# BridgeSensors.net
KiCad netlist of a schematic drawn in Altium Designer
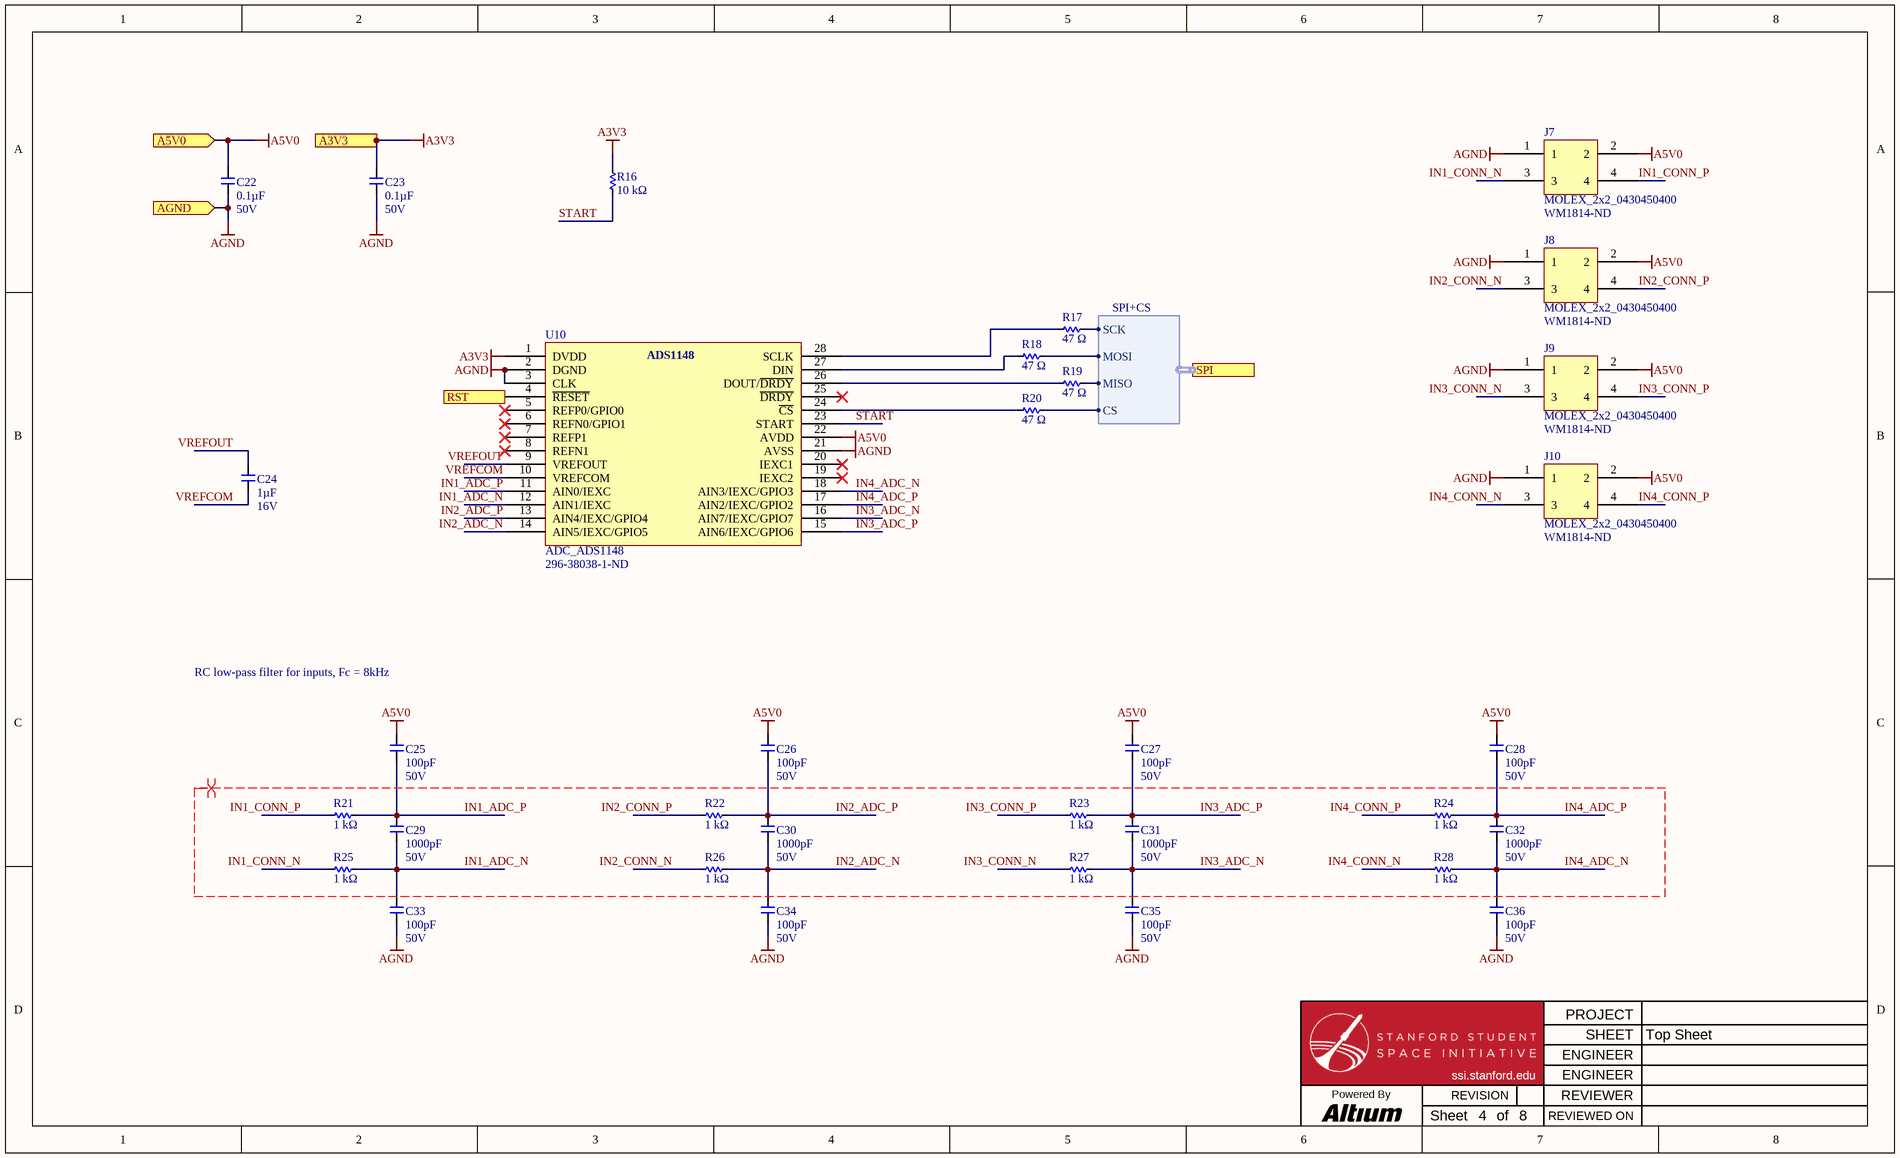
[diagram p0: BridgeSensors.SchDoc]

(export (version "E")
  (design (tool "Eeschema 10.0.6"))
  (components
    (comp (ref "C22")
      (value "__template_cap")
      (footprint "C0603")
      (description "CAP CER 0603 0.1µF X7R 50V 10%")
      (fields
        (field (name "CAPACITANCE (SHORTHAND)") "0.1µF")
        (field (name "RATED VOLTAGE") "50V")
        (field (name "MANUFACTURER") "Murata Electronics North America")
      )
      (libsource (lib "passives") (part "__template_cap"))
    )
    (comp (ref "C23")
      (value "__template_cap")
      (footprint "C0603")
      (description "CAP CER 0603 0.1µF X7R 50V 10%")
      (fields
        (field (name "CAPACITANCE (SHORTHAND)") "0.1µF")
        (field (name "RATED VOLTAGE") "50V")
        (field (name "MANUFACTURER") "Murata Electronics North America")
      )
      (libsource (lib "passives") (part "__template_cap"))
    )
    (comp (ref "C24")
      (value "__template_cap")
      (footprint "C0603")
      (description "CAP CER 0603 1µF X7R 16V 10%")
      (fields
        (field (name "CAPACITANCE (SHORTHAND)") "1µF")
        (field (name "RATED VOLTAGE") "16V")
        (field (name "MANUFACTURER") "Murata Electronics North America")
      )
      (libsource (lib "passives") (part "__template_cap"))
    )
    (comp (ref "C25")
      (value "__template_cap")
      (footprint "C0603")
      (description "CAP CER 100PF 50V C0G/NP0 0603")
      (fields
        (field (name "CAPACITANCE (SHORTHAND)") "100pF")
        (field (name "RATED VOLTAGE") "50V")
        (field (name "MANUFACTURER") "Murata Electronics North America")
      )
      (libsource (lib "passives") (part "__template_cap"))
    )
    (comp (ref "C26")
      (value "__template_cap")
      (footprint "C0603")
      (description "CAP CER 100PF 50V C0G/NP0 0603")
      (fields
        (field (name "CAPACITANCE (SHORTHAND)") "100pF")
        (field (name "RATED VOLTAGE") "50V")
        (field (name "MANUFACTURER") "Murata Electronics North America")
      )
      (libsource (lib "passives") (part "__template_cap"))
    )
    (comp (ref "C27")
      (value "__template_cap")
      (footprint "C0603")
      (description "CAP CER 100PF 50V C0G/NP0 0603")
      (fields
        (field (name "CAPACITANCE (SHORTHAND)") "100pF")
        (field (name "RATED VOLTAGE") "50V")
        (field (name "MANUFACTURER") "Murata Electronics North America")
      )
      (libsource (lib "passives") (part "__template_cap"))
    )
    (comp (ref "C28")
      (value "__template_cap")
      (footprint "C0603")
      (description "CAP CER 100PF 50V C0G/NP0 0603")
      (fields
        (field (name "CAPACITANCE (SHORTHAND)") "100pF")
        (field (name "RATED VOLTAGE") "50V")
        (field (name "MANUFACTURER") "Murata Electronics North America")
      )
      (libsource (lib "passives") (part "__template_cap"))
    )
    (comp (ref "C29")
      (value "__template_cap")
      (footprint "C0603")
      (description "CAP CER 0603 1000pF X7R 50V 10%")
      (fields
        (field (name "CAPACITANCE (SHORTHAND)") "1000pF")
        (field (name "RATED VOLTAGE") "50V")
        (field (name "MANUFACTURER") "Murata Electronics North America")
      )
      (libsource (lib "passives") (part "__template_cap"))
    )
    (comp (ref "C30")
      (value "__template_cap")
      (footprint "C0603")
      (description "CAP CER 0603 1000pF X7R 50V 10%")
      (fields
        (field (name "CAPACITANCE (SHORTHAND)") "1000pF")
        (field (name "RATED VOLTAGE") "50V")
        (field (name "MANUFACTURER") "Murata Electronics North America")
      )
      (libsource (lib "passives") (part "__template_cap"))
    )
    (comp (ref "C31")
      (value "__template_cap")
      (footprint "C0603")
      (description "CAP CER 0603 1000pF X7R 50V 10%")
      (fields
        (field (name "CAPACITANCE (SHORTHAND)") "1000pF")
        (field (name "RATED VOLTAGE") "50V")
        (field (name "MANUFACTURER") "Murata Electronics North America")
      )
      (libsource (lib "passives") (part "__template_cap"))
    )
    (comp (ref "C32")
      (value "__template_cap")
      (footprint "C0603")
      (description "CAP CER 0603 1000pF X7R 50V 10%")
      (fields
        (field (name "CAPACITANCE (SHORTHAND)") "1000pF")
        (field (name "RATED VOLTAGE") "50V")
        (field (name "MANUFACTURER") "Murata Electronics North America")
      )
      (libsource (lib "passives") (part "__template_cap"))
    )
    (comp (ref "C33")
      (value "__template_cap")
      (footprint "C0603")
      (description "CAP CER 100PF 50V C0G/NP0 0603")
      (fields
        (field (name "CAPACITANCE (SHORTHAND)") "100pF")
        (field (name "RATED VOLTAGE") "50V")
        (field (name "MANUFACTURER") "Murata Electronics North America")
      )
      (libsource (lib "passives") (part "__template_cap"))
    )
    (comp (ref "C34")
      (value "__template_cap")
      (footprint "C0603")
      (description "CAP CER 100PF 50V C0G/NP0 0603")
      (fields
        (field (name "CAPACITANCE (SHORTHAND)") "100pF")
        (field (name "RATED VOLTAGE") "50V")
        (field (name "MANUFACTURER") "Murata Electronics North America")
      )
      (libsource (lib "passives") (part "__template_cap"))
    )
    (comp (ref "C35")
      (value "__template_cap")
      (footprint "C0603")
      (description "CAP CER 100PF 50V C0G/NP0 0603")
      (fields
        (field (name "CAPACITANCE (SHORTHAND)") "100pF")
        (field (name "RATED VOLTAGE") "50V")
        (field (name "MANUFACTURER") "Murata Electronics North America")
      )
      (libsource (lib "passives") (part "__template_cap"))
    )
    (comp (ref "C36")
      (value "__template_cap")
      (footprint "C0603")
      (description "CAP CER 100PF 50V C0G/NP0 0603")
      (fields
        (field (name "CAPACITANCE (SHORTHAND)") "100pF")
        (field (name "RATED VOLTAGE") "50V")
        (field (name "MANUFACTURER") "Murata Electronics North America")
      )
      (libsource (lib "passives") (part "__template_cap"))
    )
    (comp (ref "J7")
      (value "MOLEX_2x2_0430450400")
      (footprint "MOLEX_2x2_0430450400")
      (description "MICROFIT CONN HEADER R/A 4POS 3MM")
      (fields (field (name "SUPPLIER PART NUMBER 1") "WM1814-ND"))
      (libsource (lib "SSI") (part "MOLEX_2x2_0430450400"))
    )
    (comp (ref "J8")
      (value "MOLEX_2x2_0430450400")
      (footprint "MOLEX_2x2_0430450400")
      (description "MICROFIT CONN HEADER R/A 4POS 3MM")
      (fields (field (name "SUPPLIER PART NUMBER 1") "WM1814-ND"))
      (libsource (lib "SSI") (part "MOLEX_2x2_0430450400"))
    )
    (comp (ref "J9")
      (value "MOLEX_2x2_0430450400")
      (footprint "MOLEX_2x2_0430450400")
      (description "MICROFIT CONN HEADER R/A 4POS 3MM")
      (fields (field (name "SUPPLIER PART NUMBER 1") "WM1814-ND"))
      (libsource (lib "SSI") (part "MOLEX_2x2_0430450400"))
    )
    (comp (ref "J10")
      (value "MOLEX_2x2_0430450400")
      (footprint "MOLEX_2x2_0430450400")
      (description "MICROFIT CONN HEADER R/A 4POS 3MM")
      (fields (field (name "SUPPLIER PART NUMBER 1") "WM1814-ND"))
      (libsource (lib "SSI") (part "MOLEX_2x2_0430450400"))
    )
    (comp (ref "R16")
      (value "__template_resistor")
      (footprint "R0603")
      (description "RES SMD 10K OHM 1% 1/10W 0603")
      (fields
        (field (name "RESISTANCE") "10 kΩ")
        (field (name "MANUFACTURER PART NUMBER") "RC0603FR-0710KL")
        (field (name "MANUFACTURER") "Yageo")
      )
      (libsource (lib "passives") (part "__template_resistor"))
    )
    (comp (ref "R17")
      (value "__template_resistor")
      (footprint "R0603")
      (description "RES SMD 47 OHM 1% 1/10W 0603")
      (fields
        (field (name "RESISTANCE") "47 Ω")
        (field (name "MANUFACTURER PART NUMBER") "RC0603FR-0747RL")
        (field (name "MANUFACTURER") "Yageo")
      )
      (libsource (lib "passives") (part "__template_resistor"))
    )
    (comp (ref "R18")
      (value "__template_resistor")
      (footprint "R0603")
      (description "RES SMD 47 OHM 1% 1/10W 0603")
      (fields
        (field (name "RESISTANCE") "47 Ω")
        (field (name "MANUFACTURER PART NUMBER") "RC0603FR-0747RL")
        (field (name "MANUFACTURER") "Yageo")
      )
      (libsource (lib "passives") (part "__template_resistor"))
    )
    (comp (ref "R19")
      (value "__template_resistor")
      (footprint "R0603")
      (description "RES SMD 47 OHM 1% 1/10W 0603")
      (fields
        (field (name "RESISTANCE") "47 Ω")
        (field (name "MANUFACTURER PART NUMBER") "RC0603FR-0747RL")
        (field (name "MANUFACTURER") "Yageo")
      )
      (libsource (lib "passives") (part "__template_resistor"))
    )
    (comp (ref "R20")
      (value "__template_resistor")
      (footprint "R0603")
      (description "RES SMD 47 OHM 1% 1/10W 0603")
      (fields
        (field (name "RESISTANCE") "47 Ω")
        (field (name "MANUFACTURER PART NUMBER") "RC0603FR-0747RL")
        (field (name "MANUFACTURER") "Yageo")
      )
      (libsource (lib "passives") (part "__template_resistor"))
    )
    (comp (ref "R21")
      (value "__template_resistor")
      (footprint "R0603")
      (description "RES SMD 1K OHM 1% 1/10W 0603")
      (fields
        (field (name "RESISTANCE") "1 kΩ")
        (field (name "MANUFACTURER PART NUMBER") "RC0603FR-071KL")
        (field (name "MANUFACTURER") "Yageo")
      )
      (libsource (lib "passives") (part "__template_resistor"))
    )
    (comp (ref "R22")
      (value "__template_resistor")
      (footprint "R0603")
      (description "RES SMD 1K OHM 1% 1/10W 0603")
      (fields
        (field (name "RESISTANCE") "1 kΩ")
        (field (name "MANUFACTURER PART NUMBER") "RC0603FR-071KL")
        (field (name "MANUFACTURER") "Yageo")
      )
      (libsource (lib "passives") (part "__template_resistor"))
    )
    (comp (ref "R23")
      (value "__template_resistor")
      (footprint "R0603")
      (description "RES SMD 1K OHM 1% 1/10W 0603")
      (fields
        (field (name "RESISTANCE") "1 kΩ")
        (field (name "MANUFACTURER PART NUMBER") "RC0603FR-071KL")
        (field (name "MANUFACTURER") "Yageo")
      )
      (libsource (lib "passives") (part "__template_resistor"))
    )
    (comp (ref "R24")
      (value "__template_resistor")
      (footprint "R0603")
      (description "RES SMD 1K OHM 1% 1/10W 0603")
      (fields
        (field (name "RESISTANCE") "1 kΩ")
        (field (name "MANUFACTURER PART NUMBER") "RC0603FR-071KL")
        (field (name "MANUFACTURER") "Yageo")
      )
      (libsource (lib "passives") (part "__template_resistor"))
    )
    (comp (ref "R25")
      (value "__template_resistor")
      (footprint "R0603")
      (description "RES SMD 1K OHM 1% 1/10W 0603")
      (fields
        (field (name "RESISTANCE") "1 kΩ")
        (field (name "MANUFACTURER PART NUMBER") "RC0603FR-071KL")
        (field (name "MANUFACTURER") "Yageo")
      )
      (libsource (lib "passives") (part "__template_resistor"))
    )
    (comp (ref "R26")
      (value "__template_resistor")
      (footprint "R0603")
      (description "RES SMD 1K OHM 1% 1/10W 0603")
      (fields
        (field (name "RESISTANCE") "1 kΩ")
        (field (name "MANUFACTURER PART NUMBER") "RC0603FR-071KL")
        (field (name "MANUFACTURER") "Yageo")
      )
      (libsource (lib "passives") (part "__template_resistor"))
    )
    (comp (ref "R27")
      (value "__template_resistor")
      (footprint "R0603")
      (description "RES SMD 1K OHM 1% 1/10W 0603")
      (fields
        (field (name "RESISTANCE") "1 kΩ")
        (field (name "MANUFACTURER PART NUMBER") "RC0603FR-071KL")
        (field (name "MANUFACTURER") "Yageo")
      )
      (libsource (lib "passives") (part "__template_resistor"))
    )
    (comp (ref "R28")
      (value "__template_resistor")
      (footprint "R0603")
      (description "RES SMD 1K OHM 1% 1/10W 0603")
      (fields
        (field (name "RESISTANCE") "1 kΩ")
        (field (name "MANUFACTURER PART NUMBER") "RC0603FR-071KL")
        (field (name "MANUFACTURER") "Yageo")
      )
      (libsource (lib "passives") (part "__template_resistor"))
    )
    (comp (ref "U10")
      (value "ADC_ADS1148")
      (footprint "28TSSOP65")
      (description "IC ADC 16BIT SRL 2KSPS 28TSSOP")
      (fields (field (name "SUPPLIER PART NUMBER 1") "296-38038-1-ND"))
      (libsource (lib "SSI") (part "ADC_ADS1148"))
    )
  )
  (nets
    (net (code "2") (name "/CS") (class "Default") (node (ref "R20") (pin "2") (pintype "passive")))
    (net (code "3") (name "/IN1_ADC_N") (class "Default")
      (node (ref "C29") (pin "1") (pintype "passive"))
      (node (ref "C33") (pin "1") (pintype "passive"))
      (node (ref "R25") (pin "2") (pintype "passive"))
      (node (ref "U10") (pin "12") (pinfunction "AIN1/IEXC_12") (pintype "passive"))
    )
    (net (code "4") (name "/IN1_ADC_P") (class "Default")
      (node (ref "C25") (pin "1") (pintype "passive"))
      (node (ref "C29") (pin "2") (pintype "passive"))
      (node (ref "R21") (pin "2") (pintype "passive"))
      (node (ref "U10") (pin "11") (pinfunction "AIN0/IEXC_11") (pintype "passive"))
    )
    (net (code "5") (name "/IN1_CONN_N") (class "Default")
      (node (ref "J7") (pin "3") (pinfunction "3_3") (pintype "passive"))
      (node (ref "R25") (pin "1") (pintype "passive"))
    )
    (net (code "6") (name "/IN1_CONN_P") (class "Default")
      (node (ref "J7") (pin "4") (pinfunction "4_4") (pintype "passive"))
      (node (ref "R21") (pin "1") (pintype "passive"))
    )
    (net (code "7") (name "/IN2_ADC_N") (class "Default")
      (node (ref "C30") (pin "1") (pintype "passive"))
      (node (ref "C34") (pin "1") (pintype "passive"))
      (node (ref "R26") (pin "2") (pintype "passive"))
      (node (ref "U10") (pin "14") (pinfunction "AIN5/IEXC/GPIO5_14") (pintype "passive"))
    )
    (net (code "8") (name "/IN2_ADC_P") (class "Default")
      (node (ref "C26") (pin "1") (pintype "passive"))
      (node (ref "C30") (pin "2") (pintype "passive"))
      (node (ref "R22") (pin "2") (pintype "passive"))
      (node (ref "U10") (pin "13") (pinfunction "AIN4/IEXC/GPIO4_13") (pintype "passive"))
    )
    (net (code "9") (name "/IN2_CONN_N") (class "Default")
      (node (ref "J8") (pin "3") (pinfunction "3_3") (pintype "passive"))
      (node (ref "R26") (pin "1") (pintype "passive"))
    )
    (net (code "10") (name "/IN2_CONN_P") (class "Default")
      (node (ref "J8") (pin "4") (pinfunction "4_4") (pintype "passive"))
      (node (ref "R22") (pin "1") (pintype "passive"))
    )
    (net (code "11") (name "/IN3_ADC_N") (class "Default")
      (node (ref "C31") (pin "1") (pintype "passive"))
      (node (ref "C35") (pin "1") (pintype "passive"))
      (node (ref "R27") (pin "2") (pintype "passive"))
      (node (ref "U10") (pin "16") (pinfunction "AIN7/IEXC/GPIO7_16") (pintype "passive"))
    )
    (net (code "12") (name "/IN3_ADC_P") (class "Default")
      (node (ref "C27") (pin "1") (pintype "passive"))
      (node (ref "C31") (pin "2") (pintype "passive"))
      (node (ref "R23") (pin "2") (pintype "passive"))
      (node (ref "U10") (pin "15") (pinfunction "AIN6/IEXC/GPIO6_15") (pintype "passive"))
    )
    (net (code "13") (name "/IN3_CONN_N") (class "Default")
      (node (ref "J9") (pin "3") (pinfunction "3_3") (pintype "passive"))
      (node (ref "R27") (pin "1") (pintype "passive"))
    )
    (net (code "14") (name "/IN3_CONN_P") (class "Default")
      (node (ref "J9") (pin "4") (pinfunction "4_4") (pintype "passive"))
      (node (ref "R23") (pin "1") (pintype "passive"))
    )
    (net (code "15") (name "/IN4_ADC_N") (class "Default")
      (node (ref "C32") (pin "1") (pintype "passive"))
      (node (ref "C36") (pin "1") (pintype "passive"))
      (node (ref "R28") (pin "2") (pintype "passive"))
      (node (ref "U10") (pin "18") (pinfunction "AIN3/IEXC/GPIO3_18") (pintype "passive"))
    )
    (net (code "16") (name "/IN4_ADC_P") (class "Default")
      (node (ref "C28") (pin "1") (pintype "passive"))
      (node (ref "C32") (pin "2") (pintype "passive"))
      (node (ref "R24") (pin "2") (pintype "passive"))
      (node (ref "U10") (pin "17") (pinfunction "AIN2/IEXC/GPIO2_17") (pintype "passive"))
    )
    (net (code "17") (name "/IN4_CONN_N") (class "Default")
      (node (ref "J10") (pin "3") (pinfunction "3_3") (pintype "passive"))
      (node (ref "R28") (pin "1") (pintype "passive"))
    )
    (net (code "18") (name "/IN4_CONN_P") (class "Default")
      (node (ref "J10") (pin "4") (pinfunction "4_4") (pintype "passive"))
      (node (ref "R24") (pin "1") (pintype "passive"))
    )
    (net (code "19") (name "/MISO") (class "Default") (node (ref "R19") (pin "2") (pintype "passive")))
    (net (code "20") (name "/MOSI") (class "Default") (node (ref "R18") (pin "2") (pintype "passive")))
    (net (code "21") (name "/RST") (class "Default")
      (node (ref "U10") (pin "4") (pinfunction "~{RESET}_4") (pintype "passive"))
    )
    (net (code "22") (name "/SCK") (class "Default") (node (ref "R17") (pin "2") (pintype "passive")))
    (net (code "23") (name "/START") (class "Default")
      (node (ref "R16") (pin "1") (pintype "passive"))
      (node (ref "U10") (pin "23") (pinfunction "START_23") (pintype "passive"))
    )
    (net (code "24") (name "/VREFCOM") (class "Default")
      (node (ref "C24") (pin "2") (pintype "passive"))
      (node (ref "U10") (pin "10") (pinfunction "VREFCOM_10") (pintype "passive"))
    )
    (net (code "25") (name "/VREFOUT") (class "Default")
      (node (ref "C24") (pin "1") (pintype "passive"))
      (node (ref "U10") (pin "9") (pinfunction "VREFOUT_9") (pintype "passive"))
    )
    (net (code "27") (name "A3V3") (class "Default")
      (node (ref "C23") (pin "1") (pintype "passive"))
      (node (ref "R16") (pin "2") (pintype "passive"))
      (node (ref "U10") (pin "1") (pinfunction "DVDD_1") (pintype "passive"))
    )
    (net (code "28") (name "A5V0") (class "Default")
      (node (ref "C22") (pin "1") (pintype "passive"))
      (node (ref "C25") (pin "2") (pintype "passive"))
      (node (ref "C26") (pin "2") (pintype "passive"))
      (node (ref "C27") (pin "2") (pintype "passive"))
      (node (ref "C28") (pin "2") (pintype "passive"))
      (node (ref "J10") (pin "2") (pinfunction "2_2") (pintype "passive"))
      (node (ref "J7") (pin "2") (pinfunction "2_2") (pintype "passive"))
      (node (ref "J8") (pin "2") (pinfunction "2_2") (pintype "passive"))
      (node (ref "J9") (pin "2") (pinfunction "2_2") (pintype "passive"))
      (node (ref "U10") (pin "22") (pinfunction "AVDD_22") (pintype "passive"))
    )
    (net (code "29") (name "AGND") (class "Default")
      (node (ref "C22") (pin "2") (pintype "passive"))
      (node (ref "C23") (pin "2") (pintype "passive"))
      (node (ref "C33") (pin "2") (pintype "passive"))
      (node (ref "C34") (pin "2") (pintype "passive"))
      (node (ref "C35") (pin "2") (pintype "passive"))
      (node (ref "C36") (pin "2") (pintype "passive"))
      (node (ref "J10") (pin "1") (pinfunction "1_1") (pintype "passive"))
      (node (ref "J7") (pin "1") (pinfunction "1_1") (pintype "passive"))
      (node (ref "J8") (pin "1") (pinfunction "1_1") (pintype "passive"))
      (node (ref "J9") (pin "1") (pinfunction "1_1") (pintype "passive"))
      (node (ref "U10") (pin "2") (pinfunction "DGND_2") (pintype "passive"))
      (node (ref "U10") (pin "21") (pinfunction "AVSS_21") (pintype "passive"))
      (node (ref "U10") (pin "3") (pinfunction "CLK_3") (pintype "passive"))
    )
    (net (code "30") (name "Net-(U10-DIN)") (class "Default")
      (node (ref "R18") (pin "1") (pintype "passive"))
      (node (ref "U10") (pin "27") (pinfunction "DIN_27") (pintype "passive"))
    )
    (net (code "31") (name "Net-(U10-DOUT{slash}~{DRDY})") (class "Default")
      (node (ref "R19") (pin "1") (pintype "passive"))
      (node (ref "U10") (pin "26") (pinfunction "DOUT/~{DRDY}_26") (pintype "passive"))
    )
    (net (code "32") (name "Net-(U10-SCLK)") (class "Default")
      (node (ref "R17") (pin "1") (pintype "passive"))
      (node (ref "U10") (pin "28") (pinfunction "SCLK_28") (pintype "passive"))
    )
    (net (code "33") (name "Net-(U10-~{CS})") (class "Default")
      (node (ref "R20") (pin "1") (pintype "passive"))
      (node (ref "U10") (pin "24") (pinfunction "~{CS}_24") (pintype "passive"))
    )
    (net (code "34") (name "unconnected-(U10-IEXC1-Pad20)") (class "Default")
      (node (ref "U10") (pin "20") (pinfunction "IEXC1_20") (pintype "passive+no_connect"))
    )
    (net (code "35") (name "unconnected-(U10-IEXC2-Pad19)") (class "Default")
      (node (ref "U10") (pin "19") (pinfunction "IEXC2_19") (pintype "passive+no_connect"))
    )
    (net (code "36") (name "unconnected-(U10-REFN0{slash}GPIO1-Pad6)") (class "Default")
      (node (ref "U10") (pin "6") (pinfunction "REFN0/GPIO1_6") (pintype "passive+no_connect"))
    )
    (net (code "37") (name "unconnected-(U10-REFN1-Pad8)") (class "Default")
      (node (ref "U10") (pin "8") (pinfunction "REFN1_8") (pintype "passive+no_connect"))
    )
    (net (code "38") (name "unconnected-(U10-REFP0{slash}GPIO0-Pad5)") (class "Default")
      (node (ref "U10") (pin "5") (pinfunction "REFP0/GPIO0_5") (pintype "passive+no_connect"))
    )
    (net (code "39") (name "unconnected-(U10-REFP1-Pad7)") (class "Default")
      (node (ref "U10") (pin "7") (pinfunction "REFP1_7") (pintype "passive+no_connect"))
    )
    (net (code "40") (name "unconnected-(U10-~{DRDY}-Pad25)") (class "Default")
      (node (ref "U10") (pin "25") (pinfunction "~{DRDY}_25") (pintype "passive+no_connect"))
    )
  )
)
